# Rover_Optical_Dust_Sensor.net
KiCad netlist of a schematic drawn in EAGLE
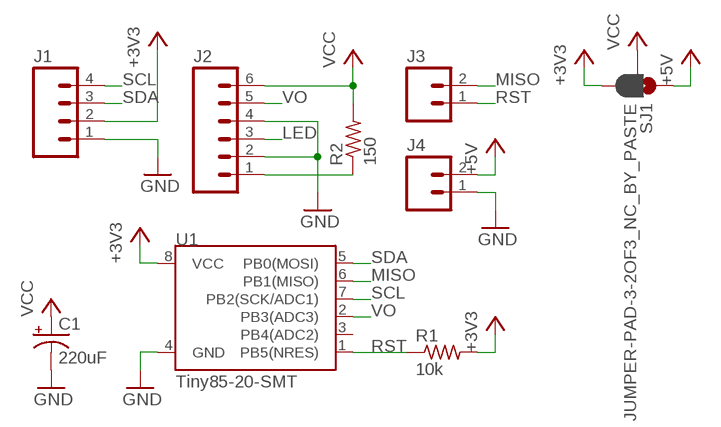
[diagram p0: schematic, sheet 1]

(export (version "E")
  (design (tool "Eeschema 10.0.6"))
  (components
    (comp (ref "C1")
      (value "220uF")
      (footprint "eagle-import:CPOL-RADIAL-100UF-25V")
      (libsource (lib "eagle-import") (part "CAP_POLPTH1"))
    )
    (comp (ref "J1")
      (value "1X04M-0.1-PTH")
      (footprint "eagle-import:M-1X04-0.1-PTH")
      (libsource (lib "eagle-import") (part "1X04M-0.1-PTH"))
    )
    (comp (ref "J2")
      (value "1X06M-0.1-PTH")
      (footprint "eagle-import:M-1X06-0.1-PTH")
      (libsource (lib "eagle-import") (part "1X06M-0.1-PTH"))
    )
    (comp (ref "J3")
      (value "1X02M-0.1-PTH")
      (footprint "eagle-import:M-1X02-0.1-PTH")
      (libsource (lib "eagle-import") (part "1X02M-0.1-PTH"))
    )
    (comp (ref "J4")
      (value "1X02M-0.1-PTH")
      (footprint "eagle-import:M-1X02-0.1-PTH")
      (libsource (lib "eagle-import") (part "1X02M-0.1-PTH"))
    )
    (comp (ref "R1")
      (value "10k")
      (footprint "eagle-import:R0603")
      (libsource (lib "eagle-import") (part "RESISTOR0603"))
    )
    (comp (ref "R2")
      (value "150")
      (footprint "eagle-import:R0603")
      (libsource (lib "eagle-import") (part "RESISTOR0603"))
    )
    (comp (ref "SJ1")
      (value "JUMPER-PAD-3-2OF3_NC_BY_PASTE")
      (footprint "eagle-import:PAD-JUMPER-3-2OF3_NC_BY_PASTE_YES_SILK_FULL_BOX")
      (libsource (lib "eagle-import") (part "JUMPER-PAD-3-2OF3_NC_BY_PASTE"))
    )
    (comp (ref "U1")
      (value "Tiny85-20-SMT")
      (footprint "eagle-import:SO08-EIAJ")
      (libsource (lib "eagle-import") (part "ATTINY45TINY85-20-SMT"))
    )
  )
  (nets
    (net (code "1") (name "+3V3") (class "Default")
      (node (ref "J1") (pin "2") (pinfunction "2_2") (pintype "passive"))
      (node (ref "R1") (pin "2") (pinfunction "2_2") (pintype "passive"))
      (node (ref "SJ1") (pin "3") (pinfunction "3_3") (pintype "passive"))
      (node (ref "U1") (pin "8") (pinfunction "VCC_8") (pintype "bidirectional"))
    )
    (net (code "2") (name "+5V") (class "Default")
      (node (ref "J4") (pin "2") (pinfunction "2_2") (pintype "passive"))
      (node (ref "SJ1") (pin "1") (pinfunction "1_1") (pintype "passive"))
    )
    (net (code "3") (name "/LED") (class "Default")
      (node (ref "J2") (pin "3") (pinfunction "3_3") (pintype "passive"))
    )
    (net (code "4") (name "/MISO") (class "Default")
      (node (ref "J3") (pin "2") (pinfunction "2_2") (pintype "passive"))
      (node (ref "U1") (pin "6") (pinfunction "PB1(MISO)_6") (pintype "bidirectional"))
    )
    (net (code "5") (name "/RST") (class "Default")
      (node (ref "J3") (pin "1") (pinfunction "1_1") (pintype "passive"))
      (node (ref "R1") (pin "1") (pinfunction "1_1") (pintype "passive"))
      (node (ref "U1") (pin "1") (pinfunction "PB5(NRES)_1") (pintype "bidirectional"))
    )
    (net (code "6") (name "/SCL") (class "Default")
      (node (ref "J1") (pin "4") (pinfunction "4_4") (pintype "passive"))
      (node (ref "U1") (pin "7") (pinfunction "PB2(SCK/ADC1)_7") (pintype "bidirectional"))
    )
    (net (code "7") (name "/SDA") (class "Default")
      (node (ref "J1") (pin "3") (pinfunction "3_3") (pintype "passive"))
      (node (ref "U1") (pin "5") (pinfunction "PB0(MOSI)_5") (pintype "bidirectional"))
    )
    (net (code "8") (name "/VO") (class "Default")
      (node (ref "J2") (pin "5") (pinfunction "5_5") (pintype "passive"))
      (node (ref "U1") (pin "2") (pinfunction "PB3(ADC3)_2") (pintype "bidirectional"))
    )
    (net (code "9") (name "GND") (class "Default")
      (node (ref "C1") (pin "2") (pinfunction "-_2") (pintype "passive"))
      (node (ref "J1") (pin "1") (pinfunction "1_1") (pintype "passive"))
      (node (ref "J2") (pin "2") (pinfunction "2_2") (pintype "passive"))
      (node (ref "J2") (pin "4") (pinfunction "4_4") (pintype "passive"))
      (node (ref "J4") (pin "1") (pinfunction "1_1") (pintype "passive"))
      (node (ref "U1") (pin "4") (pinfunction "GND_4") (pintype "bidirectional"))
    )
    (net (code "10") (name "Net-(J2-Pad1)") (class "Default")
      (node (ref "J2") (pin "1") (pinfunction "1_1") (pintype "passive"))
      (node (ref "R2") (pin "1") (pinfunction "1_1") (pintype "passive"))
    )
    (net (code "11") (name "VCC") (class "Default")
      (node (ref "C1") (pin "1") (pinfunction "+_1") (pintype "passive"))
      (node (ref "J2") (pin "6") (pinfunction "6_6") (pintype "passive"))
      (node (ref "R2") (pin "2") (pinfunction "2_2") (pintype "passive"))
      (node (ref "SJ1") (pin "2") (pinfunction "2_2") (pintype "passive"))
    )
    (net (code "12") (name "unconnected-(U1-PB4(ADC2)-Pad3)") (class "Default")
      (node (ref "U1") (pin "3") (pinfunction "PB4(ADC2)_3") (pintype "bidirectional"))
    )
  )
)
